# imbuelight_move_detection.net
KiCad netlist of a schematic drawn in Altium Designer
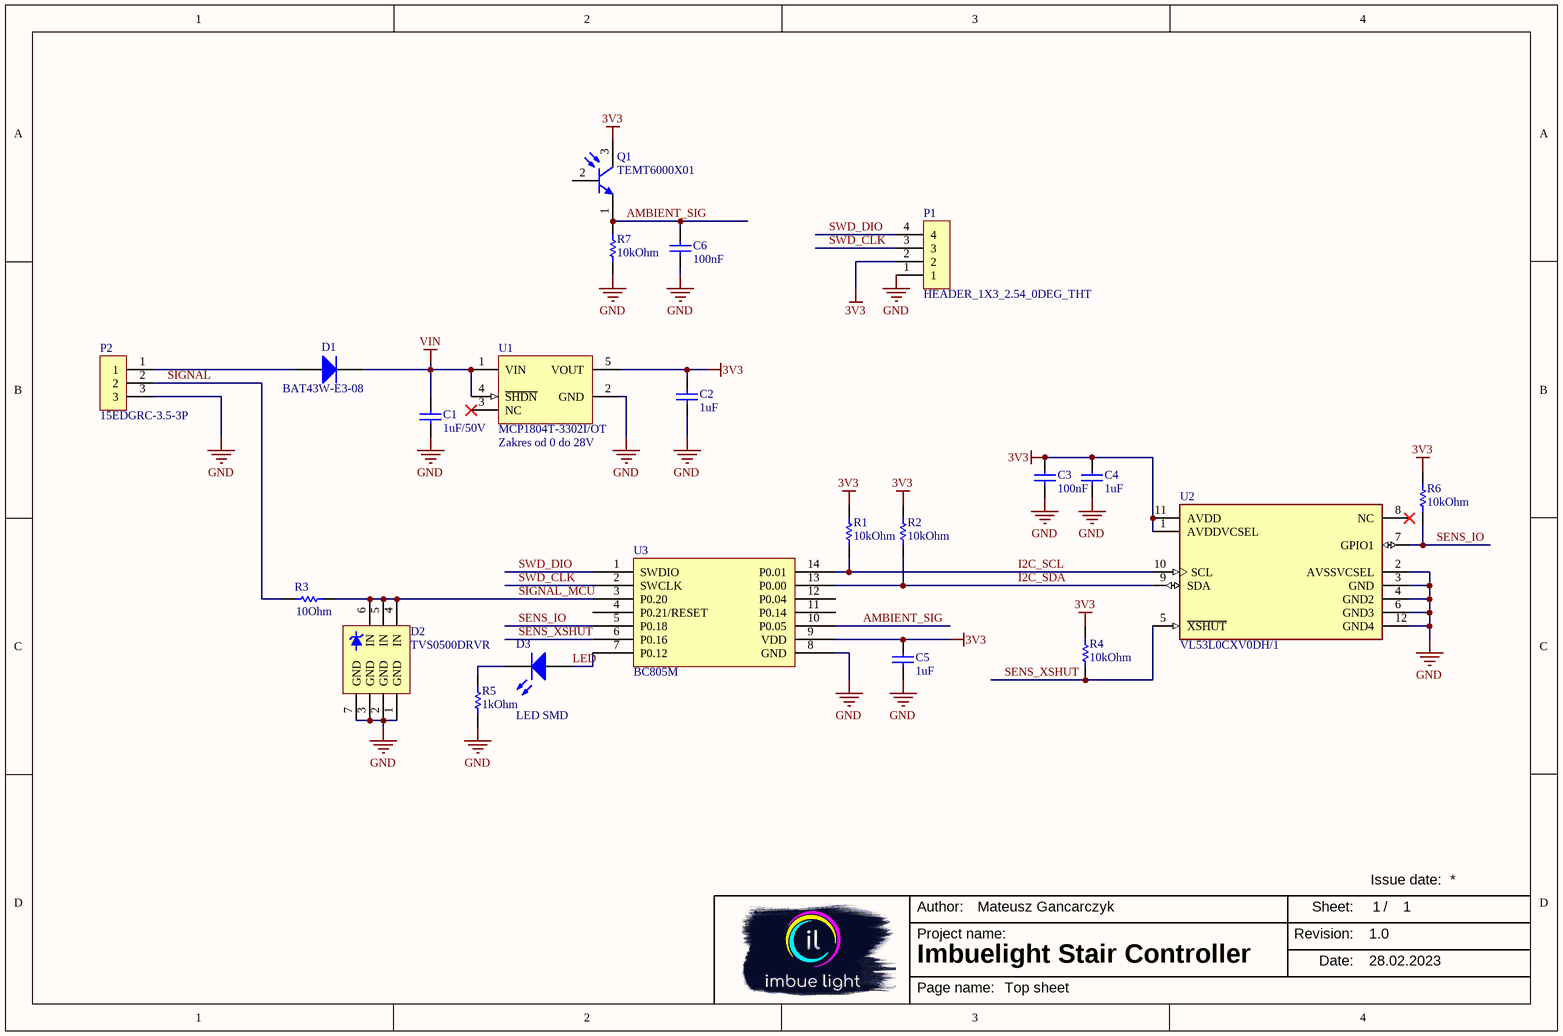
[diagram p0: imbuelight_move_detection.SchDoc]

(export (version "E")
  (design (tool "Eeschema 10.0.6"))
  (components
    (comp (ref "C1")
      (value "0805 1uF 20V")
      (footprint "CAP_SMD_0805")
      (description "Capacitor")
      (fields (field (name "WARTOŚĆ") "1uF/50V"))
      (libsource (lib "MY_LIB") (part "Capacitor SMD"))
    )
    (comp (ref "C2")
      (value "0603 1uF 10V")
      (footprint "CAP_SMD_0603")
      (description "Capacitor")
      (fields (field (name "WARTOŚĆ") "1uF"))
      (libsource (lib "MY_LIB") (part "Capacitor SMD"))
    )
    (comp (ref "C3")
      (value "0603 1uF 10V")
      (footprint "CAP_SMD_0603")
      (description "Capacitor")
      (fields (field (name "WARTOŚĆ") "100nF"))
      (libsource (lib "MY_LIB") (part "Capacitor SMD"))
    )
    (comp (ref "C4")
      (value "0603 1uF 10V")
      (footprint "CAP_SMD_0603")
      (description "Capacitor")
      (fields (field (name "WARTOŚĆ") "1uF"))
      (libsource (lib "MY_LIB") (part "Capacitor SMD"))
    )
    (comp (ref "C5")
      (value "0603 1uF 10V")
      (footprint "CAP_SMD_0603")
      (description "Capacitor")
      (fields (field (name "WARTOŚĆ") "1uF"))
      (libsource (lib "MY_LIB") (part "Capacitor SMD"))
    )
    (comp (ref "C6")
      (value "0603 1uF 10V")
      (footprint "CAP_SMD_0603")
      (description "Capacitor")
      (fields (field (name "WARTOŚĆ") "100nF"))
      (libsource (lib "MY_LIB") (part "Capacitor SMD"))
    )
    (comp (ref "D1")
      (value "BAT43W-E3-08")
      (footprint "SOD-123")
      (description "Dioda SMD")
      (fields (field (name "WARTOŚĆ") "BAT43W-E3-08"))
      (libsource (lib "MY_LIB") (part "Dioda SMD"))
    )
    (comp (ref "D2")
      (value "TVS0500DRVR")
      (footprint "FP-DRV0006A-IPC_C")
      (description "ESD Suppressors / TVS Diodes 5V flat-clamp surge protection device 6-WSON -40 to 125")
      (libsource (lib "MY_LIB") (part "TVS0500DRVR"))
    )
    (comp (ref "D3")
      (value "Dioda LED SMD 1206")
      (footprint "LED SMD 1206")
      (fields (field (name "WARTOŚĆ") "LED SMD"))
      (libsource (lib "MY_LIB") (part "Dioda LED SMD 1206"))
    )
    (comp (ref "P1")
      (value "HEADER_1X3_2.54_0DEG_THT")
      (footprint "HDR1X4")
      (description "4pin 1x4 2.54mm 0.100\" pitch header vertical tht")
      (libsource (lib "MY_LIB") (part "Header 1x4"))
    )
    (comp (ref "P2")
      (value "15EDGRC-3.5-3P")
      (footprint "15EDGVC-3.5-03P-14-00A(H)")
      (description "15EDGVC-3.5-03P-14-00A(H) - 3 pin")
      (libsource (lib "MY_LIB") (part "15EDGVC-3.5-03P-14-00A(H)"))
    )
    (comp (ref "Q1")
      (value "TEMT6000X01")
      (footprint "VSIL-TEMT6000X01_V")
      (description "Ambient Light Sensor\r\n, 100 mW, -40 to 100 degC, 3-Pin SMD, RoHS, Tape and Reel")
      (libsource (lib "Altium Content Vault") (part "PHOTO-NPN-EBC-3"))
    )
    (comp (ref "R1")
      (value "0603 10kOhm 1%")
      (footprint "RES_0603")
      (description "Generic Resistor SMD")
      (fields (field (name "RESISTANCE") "10kOhm"))
      (libsource (lib "MY_LIB") (part "Resistor SMD_1"))
    )
    (comp (ref "R2")
      (value "0603 10kOhm 1%")
      (footprint "RES_0603")
      (description "Generic Resistor SMD")
      (fields (field (name "RESISTANCE") "10kOhm"))
      (libsource (lib "MY_LIB") (part "Resistor SMD_1"))
    )
    (comp (ref "R3")
      (value "0603 10Ohm 1%")
      (footprint "RES_0603")
      (description "Generic Resistor SMD")
      (fields (field (name "RESISTANCE") "10Ohm"))
      (libsource (lib "MY_LIB") (part "Resistor SMD_1"))
    )
    (comp (ref "R4")
      (value "0603 10kOhm 1%")
      (footprint "RES_0603")
      (description "Generic Resistor SMD")
      (fields (field (name "RESISTANCE") "10kOhm"))
      (libsource (lib "MY_LIB") (part "Resistor SMD_1"))
    )
    (comp (ref "R5")
      (value "0603 1kOhm 1%")
      (footprint "RES_0603")
      (description "Generic Resistor SMD")
      (fields (field (name "RESISTANCE") "1kOhm"))
      (libsource (lib "MY_LIB") (part "Resistor SMD_1"))
    )
    (comp (ref "R6")
      (value "0603 10kOhm 1%")
      (footprint "RES_0603")
      (description "Generic Resistor SMD")
      (fields (field (name "RESISTANCE") "10kOhm"))
      (libsource (lib "MY_LIB") (part "Resistor SMD_1"))
    )
    (comp (ref "R7")
      (value "0603 10kOhm 1%")
      (footprint "RES_0603")
      (description "Generic Resistor SMD")
      (fields (field (name "RESISTANCE") "10kOhm"))
      (libsource (lib "MY_LIB") (part "Resistor SMD_1"))
    )
    (comp (ref "U1")
      (value "MCP1804T-3302I/OT")
      (footprint "SOT-23-5")
      (description "Regulatro LDO 3,3V")
      (fields (field (name "MANUFACTURER") "Microchip"))
      (libsource (lib "MY_LIB") (part "MCP1804T-3302I/OT"))
    )
    (comp (ref "U2")
      (value "VL53L0CXV0DH/1")
      (footprint "FP-LGA-12-MFG")
      (description "SENSOR OPTICAL 200CM I2C")
      (fields
        (field (name "OCTOPART") "https://octopart.com/vl53l0cxv0dh%2F1-stmicroelectronics-71168165")
        (field (name "MANUFACTURER") "STMicroelectronics")
      )
      (libsource (lib "MY_LIB") (part "VL53L0CXV0DH/1"))
    )
    (comp (ref "U3")
      (value "BC805M")
      (footprint "BC805")
      (description "Bluetooth Low Energy (BLE) 5 Module")
      (libsource (lib "MY_LIB") (part "BC805M"))
    )
  )
  (nets
    (net (code "1") (name "/AMBIENT_SIG") (class "Default")
      (node (ref "C6") (pin "2") (pinfunction "2_2") (pintype "passive"))
      (node (ref "Q1") (pin "1") (pinfunction "E_1") (pintype "passive"))
      (node (ref "R7") (pin "1") (pinfunction "1_1") (pintype "passive"))
      (node (ref "U3") (pin "10") (pinfunction "P0.05_10") (pintype "passive"))
    )
    (net (code "2") (name "/I2C_SCL") (class "Default")
      (node (ref "R1") (pin "2") (pinfunction "2_2") (pintype "passive"))
      (node (ref "U2") (pin "10") (pinfunction "SCL_10") (pintype "input"))
      (node (ref "U3") (pin "14") (pinfunction "P0.01_14") (pintype "passive"))
    )
    (net (code "3") (name "/I2C_SDA") (class "Default")
      (node (ref "R2") (pin "2") (pinfunction "2_2") (pintype "passive"))
      (node (ref "U2") (pin "9") (pinfunction "SDA_9") (pintype "bidirectional"))
      (node (ref "U3") (pin "13") (pinfunction "P0.00_13") (pintype "passive"))
    )
    (net (code "4") (name "/LED") (class "Default")
      (node (ref "D3") (pin "A") (pinfunction "A_A") (pintype "passive"))
      (node (ref "U3") (pin "7") (pinfunction "P0.12_7") (pintype "passive"))
    )
    (net (code "5") (name "/SENS_IO") (class "Default")
      (node (ref "R6") (pin "2") (pinfunction "2_2") (pintype "passive"))
      (node (ref "U2") (pin "7") (pinfunction "GPIO1_7") (pintype "bidirectional"))
      (node (ref "U3") (pin "5") (pinfunction "P0.18_5") (pintype "passive"))
    )
    (net (code "6") (name "/SENS_XSHUT") (class "Default")
      (node (ref "R4") (pin "1") (pinfunction "1_1") (pintype "passive"))
      (node (ref "U2") (pin "5") (pinfunction "~{XSHUT}_5") (pintype "input"))
      (node (ref "U3") (pin "6") (pinfunction "P0.16_6") (pintype "passive"))
    )
    (net (code "7") (name "/SIGNAL") (class "Default")
      (node (ref "P2") (pin "2") (pinfunction "2_2") (pintype "passive"))
      (node (ref "R3") (pin "1") (pinfunction "1_1") (pintype "passive"))
    )
    (net (code "8") (name "/SIGNAL_MCU") (class "Default")
      (node (ref "D2") (pin "4") (pinfunction "IN_4") (pintype "passive"))
      (node (ref "D2") (pin "5") (pinfunction "IN_5") (pintype "passive"))
      (node (ref "D2") (pin "6") (pinfunction "IN_6") (pintype "passive"))
      (node (ref "R3") (pin "2") (pinfunction "2_2") (pintype "passive"))
      (node (ref "U3") (pin "3") (pinfunction "P0.20_3") (pintype "passive"))
    )
    (net (code "9") (name "/SWD_CLK") (class "Default")
      (node (ref "P1") (pin "3") (pinfunction "3_3") (pintype "passive"))
      (node (ref "U3") (pin "2") (pinfunction "SWCLK_2") (pintype "passive"))
    )
    (net (code "10") (name "/SWD_DIO") (class "Default")
      (node (ref "P1") (pin "4") (pinfunction "4_4") (pintype "passive"))
      (node (ref "U3") (pin "1") (pinfunction "SWDIO_1") (pintype "passive"))
    )
    (net (code "11") (name "3V3") (class "Default")
      (node (ref "C2") (pin "2") (pinfunction "2_2") (pintype "passive"))
      (node (ref "C3") (pin "2") (pinfunction "2_2") (pintype "passive"))
      (node (ref "C4") (pin "2") (pinfunction "2_2") (pintype "passive"))
      (node (ref "C5") (pin "2") (pinfunction "2_2") (pintype "passive"))
      (node (ref "P1") (pin "2") (pinfunction "2_2") (pintype "passive"))
      (node (ref "Q1") (pin "3") (pinfunction "C_3") (pintype "passive"))
      (node (ref "R1") (pin "1") (pinfunction "1_1") (pintype "passive"))
      (node (ref "R2") (pin "1") (pinfunction "1_1") (pintype "passive"))
      (node (ref "R4") (pin "2") (pinfunction "2_2") (pintype "passive"))
      (node (ref "R6") (pin "1") (pinfunction "1_1") (pintype "passive"))
      (node (ref "U1") (pin "5") (pinfunction "VOUT_5") (pintype "power_in"))
      (node (ref "U2") (pin "1") (pinfunction "AVDDVCSEL_1") (pintype "power_in"))
      (node (ref "U2") (pin "11") (pinfunction "AVDD_11") (pintype "power_in"))
      (node (ref "U3") (pin "9") (pinfunction "VDD_9") (pintype "power_in"))
    )
    (net (code "12") (name "GND") (class "Default")
      (node (ref "C1") (pin "1") (pinfunction "1_1") (pintype "passive"))
      (node (ref "C2") (pin "1") (pinfunction "1_1") (pintype "passive"))
      (node (ref "C3") (pin "1") (pinfunction "1_1") (pintype "passive"))
      (node (ref "C4") (pin "1") (pinfunction "1_1") (pintype "passive"))
      (node (ref "C5") (pin "1") (pinfunction "1_1") (pintype "passive"))
      (node (ref "C6") (pin "1") (pinfunction "1_1") (pintype "passive"))
      (node (ref "D2") (pin "1") (pinfunction "GND_1") (pintype "power_in"))
      (node (ref "D2") (pin "2") (pinfunction "GND_2") (pintype "power_in"))
      (node (ref "D2") (pin "3") (pinfunction "GND_3") (pintype "power_in"))
      (node (ref "D2") (pin "7") (pinfunction "GND_7") (pintype "power_in"))
      (node (ref "P1") (pin "1") (pinfunction "1_1") (pintype "passive"))
      (node (ref "P2") (pin "3") (pinfunction "3_3") (pintype "passive"))
      (node (ref "R5") (pin "1") (pinfunction "1_1") (pintype "passive"))
      (node (ref "R7") (pin "2") (pinfunction "2_2") (pintype "passive"))
      (node (ref "U1") (pin "2") (pinfunction "GND_2") (pintype "power_in"))
      (node (ref "U2") (pin "12") (pinfunction "GND4_12") (pintype "power_in"))
      (node (ref "U2") (pin "2") (pinfunction "AVSSVCSEL_2") (pintype "power_in"))
      (node (ref "U2") (pin "3") (pinfunction "GND_3") (pintype "power_in"))
      (node (ref "U2") (pin "4") (pinfunction "GND2_4") (pintype "power_in"))
      (node (ref "U2") (pin "6") (pinfunction "GND3_6") (pintype "power_in"))
      (node (ref "U3") (pin "8") (pinfunction "GND_8") (pintype "power_in"))
    )
    (net (code "13") (name "Net-(D1-PadA)") (class "Default")
      (node (ref "D1") (pin "A") (pinfunction "A_A") (pintype "passive"))
      (node (ref "P2") (pin "1") (pinfunction "1_1") (pintype "passive"))
    )
    (net (code "14") (name "Net-(D3-PadK)") (class "Default")
      (node (ref "D3") (pin "K") (pinfunction "K_K") (pintype "passive"))
      (node (ref "R5") (pin "2") (pinfunction "2_2") (pintype "passive"))
    )
    (net (code "15") (name "VIN") (class "Default")
      (node (ref "C1") (pin "2") (pinfunction "2_2") (pintype "passive"))
      (node (ref "D1") (pin "K") (pinfunction "K_K") (pintype "passive"))
      (node (ref "U1") (pin "1") (pinfunction "VIN_1") (pintype "power_in"))
      (node (ref "U1") (pin "4") (pinfunction "~{SHDN}_4") (pintype "input"))
    )
    (net (code "16") (name "unconnected-(Q1-B-Pad2)") (class "Default")
      (node (ref "Q1") (pin "2") (pinfunction "B_2") (pintype "passive"))
    )
    (net (code "17") (name "unconnected-(U1-NC-Pad3)") (class "Default")
      (node (ref "U1") (pin "3") (pinfunction "NC_3") (pintype "passive+no_connect"))
    )
    (net (code "18") (name "unconnected-(U2-NC-Pad8)") (class "Default")
      (node (ref "U2") (pin "8") (pinfunction "NC_8") (pintype "passive+no_connect"))
    )
    (net (code "19") (name "unconnected-(U3-P0.04-Pad12)") (class "Default")
      (node (ref "U3") (pin "12") (pinfunction "P0.04_12") (pintype "passive"))
    )
    (net (code "20") (name "unconnected-(U3-P0.14-Pad11)") (class "Default")
      (node (ref "U3") (pin "11") (pinfunction "P0.14_11") (pintype "passive"))
    )
    (net (code "21") (name "unconnected-(U3-P0.21{slash}RESET-Pad4)") (class "Default")
      (node (ref "U3") (pin "4") (pinfunction "P0.21/RESET_4") (pintype "passive"))
    )
  )
)
